# HardwareTutorial-Controller_Board_Interf.net
KiCad netlist of a schematic drawn in Altium Designer
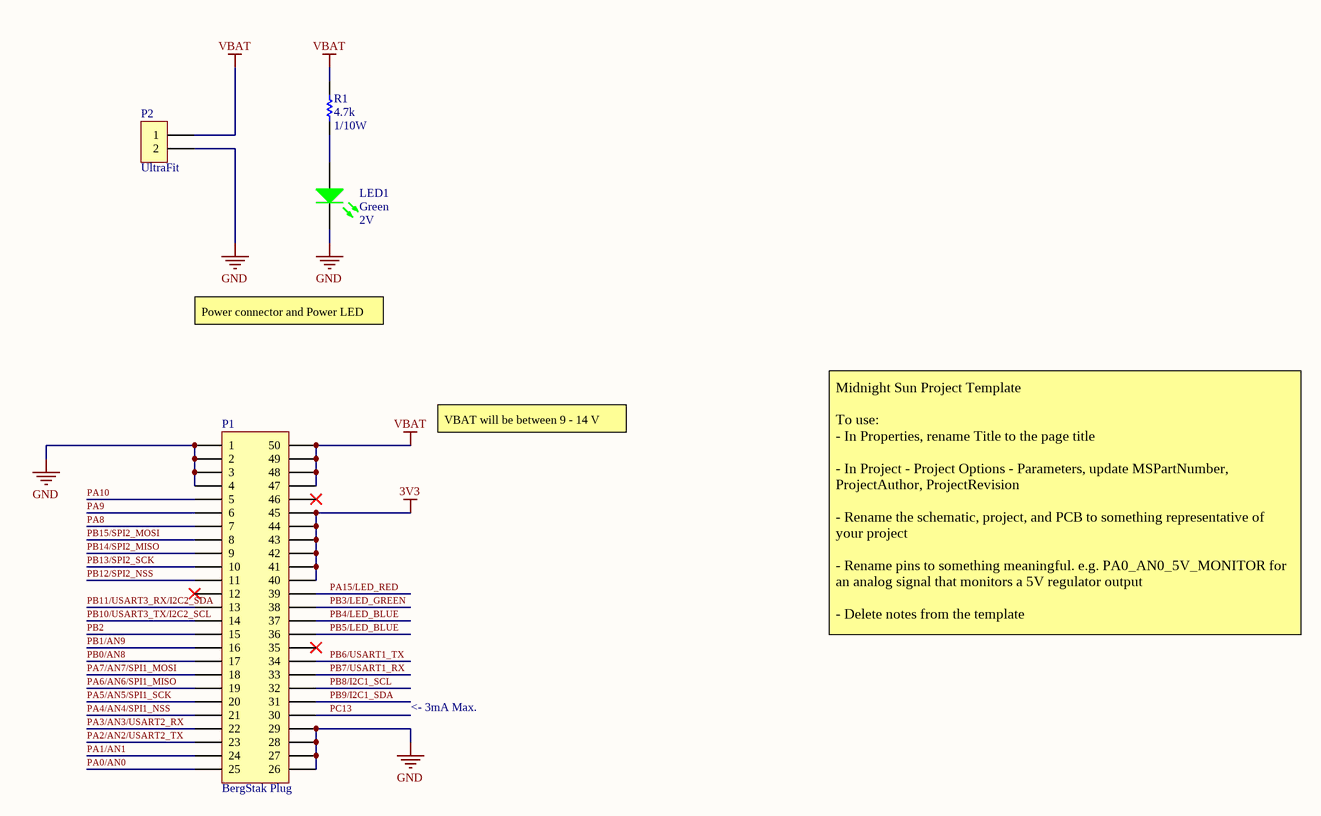
[diagram p0: HardwareTutorial-Controller_Board_Interface.SchDoc]

(export (version "E")
  (design (tool "Eeschema 10.0.6"))
  (components
    (comp (ref "LED1")
      (value "LED GREEN CLEAR 2V 0603")
      (footprint "LED_0603")
      (description "Green 572nm LED Indication - Discrete 2V 0603 (1608 Metric)")
      (fields
        (field (name "MANUFACTURER") "Wurth Electronics Inc.")
        (field (name "MANUFACTURER PART NUMBER") "150060VS75000")
        (field (name "COLOR") "Green")
        (field (name "VOLTAGE - FORWARD (VF) (TYP)") "2V")
      )
      (libsource (lib "Schematic Diagrams") (part "LED GREEN CLEAR 2V 0603"))
    )
    (comp (ref "P1")
      (value "CONN 50POS Bergstak Plug 0.02\"")
      (footprint "CONN, Bergstak 50 Pos Plug")
      (description "50 Position Connector Plug, Outer Shroud Contacts Surface Mount Gold")
      (fields (field (name "SERIES") "BergStak Plug"))
      (libsource (lib "Schematic Diagrams") (part "CONN 50POS Bergstak Plug 0.02{dblquote}"))
    )
    (comp (ref "P2")
      (value "CONN 2POS ULTRA-FIT 0.138\"")
      (footprint "CONN, 2POS ULTRA-FIT")
      (description "Connector Header Through Hole 2 position 0.138\" (3.50mm)")
      (fields
        (field (name "MANUFACTURER") "Molex")
        (field (name "MANUFACTURER PART NUMBER") "1722871102")
        (field (name "SERIES") "UltraFit")
      )
      (libsource (lib "Schematic Diagrams") (part "CONN 2POS ULTRA-FIT 0.138{dblquote}"))
    )
    (comp (ref "R1")
      (value "RES 4.7K OHM 1% 1/10W 0603")
      (footprint "RES, 0603")
      (description "4.7k Ohm ±1% 0.1W, 1/10W Chip Resistor 0603 (1608 Metric) Moisture Resistant Thick Film")
      (fields
        (field (name "TOLERANCE") "±1%")
        (field (name "RESISTANCE (OHMS)") "4.7k")
        (field (name "POWER (WATTS)") "1/10W")
      )
      (libsource (lib "Schematic Diagrams") (part "RES 4.7K OHM 1% 1/10W 0603"))
    )
  )
  (nets
    (net (code "1") (name "/PA0{slash}AN0") (class "Default")
      (node (ref "P1") (pin "25") (pinfunction "25_25") (pintype "passive"))
    )
    (net (code "2") (name "/PA1{slash}AN1") (class "Default")
      (node (ref "P1") (pin "24") (pinfunction "24_24") (pintype "passive"))
    )
    (net (code "3") (name "/PA2{slash}AN2{slash}USART2_TX") (class "Default")
      (node (ref "P1") (pin "23") (pinfunction "23_23") (pintype "passive"))
    )
    (net (code "4") (name "/PA3{slash}AN3{slash}USART2_RX") (class "Default")
      (node (ref "P1") (pin "22") (pinfunction "22_22") (pintype "passive"))
    )
    (net (code "5") (name "/PA4{slash}AN4{slash}SPI1_NSS") (class "Default")
      (node (ref "P1") (pin "21") (pinfunction "21_21") (pintype "passive"))
    )
    (net (code "6") (name "/PA5{slash}AN5{slash}SPI1_SCK") (class "Default")
      (node (ref "P1") (pin "20") (pinfunction "20_20") (pintype "passive"))
    )
    (net (code "7") (name "/PA6{slash}AN6{slash}SPI1_MISO") (class "Default")
      (node (ref "P1") (pin "19") (pinfunction "19_19") (pintype "passive"))
    )
    (net (code "8") (name "/PA7{slash}AN7{slash}SPI1_MOSI") (class "Default")
      (node (ref "P1") (pin "18") (pinfunction "18_18") (pintype "passive"))
    )
    (net (code "9") (name "/PA8") (class "Default")
      (node (ref "P1") (pin "7") (pinfunction "7_7") (pintype "passive"))
    )
    (net (code "10") (name "/PA9") (class "Default")
      (node (ref "P1") (pin "6") (pinfunction "6_6") (pintype "passive"))
    )
    (net (code "11") (name "/PA10") (class "Default")
      (node (ref "P1") (pin "5") (pinfunction "5_5") (pintype "passive"))
    )
    (net (code "12") (name "/PA15{slash}LED_RED") (class "Default")
      (node (ref "P1") (pin "39") (pinfunction "39_39") (pintype "passive"))
    )
    (net (code "13") (name "/PB0{slash}AN8") (class "Default")
      (node (ref "P1") (pin "17") (pinfunction "17_17") (pintype "passive"))
    )
    (net (code "14") (name "/PB1{slash}AN9") (class "Default")
      (node (ref "P1") (pin "16") (pinfunction "16_16") (pintype "passive"))
    )
    (net (code "15") (name "/PB2") (class "Default")
      (node (ref "P1") (pin "15") (pinfunction "15_15") (pintype "passive"))
    )
    (net (code "16") (name "/PB3{slash}LED_GREEN") (class "Default")
      (node (ref "P1") (pin "38") (pinfunction "38_38") (pintype "passive"))
    )
    (net (code "17") (name "/PB4{slash}LED_BLUE") (class "Default")
      (node (ref "P1") (pin "37") (pinfunction "37_37") (pintype "passive"))
    )
    (net (code "18") (name "/PB5{slash}LED_BLUE") (class "Default")
      (node (ref "P1") (pin "36") (pinfunction "36_36") (pintype "passive"))
    )
    (net (code "19") (name "/PB6{slash}USART1_TX") (class "Default")
      (node (ref "P1") (pin "34") (pinfunction "34_34") (pintype "passive"))
    )
    (net (code "20") (name "/PB7{slash}USART1_RX") (class "Default")
      (node (ref "P1") (pin "33") (pinfunction "33_33") (pintype "passive"))
    )
    (net (code "21") (name "/PB8{slash}I2C1_SCL") (class "Default")
      (node (ref "P1") (pin "32") (pinfunction "32_32") (pintype "passive"))
    )
    (net (code "22") (name "/PB9{slash}I2C1_SDA") (class "Default")
      (node (ref "P1") (pin "31") (pinfunction "31_31") (pintype "passive"))
    )
    (net (code "23") (name "/PB10{slash}USART3_TX{slash}I2C2_SCL") (class "Default")
      (node (ref "P1") (pin "14") (pinfunction "14_14") (pintype "passive"))
    )
    (net (code "24") (name "/PB11{slash}USART3_RX{slash}I2C2_SDA") (class "Default")
      (node (ref "P1") (pin "13") (pinfunction "13_13") (pintype "passive"))
    )
    (net (code "25") (name "/PB12{slash}SPI2_NSS") (class "Default")
      (node (ref "P1") (pin "11") (pinfunction "11_11") (pintype "passive"))
    )
    (net (code "26") (name "/PB13{slash}SPI2_SCK") (class "Default")
      (node (ref "P1") (pin "10") (pinfunction "10_10") (pintype "passive"))
    )
    (net (code "27") (name "/PB14{slash}SPI2_MISO") (class "Default")
      (node (ref "P1") (pin "9") (pinfunction "9_9") (pintype "passive"))
    )
    (net (code "28") (name "/PB15{slash}SPI2_MOSI") (class "Default")
      (node (ref "P1") (pin "8") (pinfunction "8_8") (pintype "passive"))
    )
    (net (code "29") (name "/PC13") (class "Default")
      (node (ref "P1") (pin "30") (pinfunction "30_30") (pintype "passive"))
    )
    (net (code "30") (name "3V3") (class "Default")
      (node (ref "P1") (pin "40") (pinfunction "40_40") (pintype "passive"))
      (node (ref "P1") (pin "41") (pinfunction "41_41") (pintype "passive"))
      (node (ref "P1") (pin "42") (pinfunction "42_42") (pintype "passive"))
      (node (ref "P1") (pin "43") (pinfunction "43_43") (pintype "passive"))
      (node (ref "P1") (pin "44") (pinfunction "44_44") (pintype "passive"))
      (node (ref "P1") (pin "45") (pinfunction "45_45") (pintype "passive"))
    )
    (net (code "31") (name "GND") (class "Default")
      (node (ref "LED1") (pin "2") (pinfunction "K_2") (pintype "passive"))
      (node (ref "P1") (pin "1") (pinfunction "1_1") (pintype "passive"))
      (node (ref "P1") (pin "2") (pinfunction "2_2") (pintype "passive"))
      (node (ref "P1") (pin "26") (pinfunction "26_26") (pintype "passive"))
      (node (ref "P1") (pin "27") (pinfunction "27_27") (pintype "passive"))
      (node (ref "P1") (pin "28") (pinfunction "28_28") (pintype "passive"))
      (node (ref "P1") (pin "29") (pinfunction "29_29") (pintype "passive"))
      (node (ref "P1") (pin "3") (pinfunction "3_3") (pintype "passive"))
      (node (ref "P1") (pin "4") (pinfunction "4_4") (pintype "passive"))
      (node (ref "P2") (pin "2") (pinfunction "2_2") (pintype "passive"))
    )
    (net (code "32") (name "Net-(LED1-A)") (class "Default")
      (node (ref "LED1") (pin "1") (pinfunction "A_1") (pintype "passive"))
      (node (ref "R1") (pin "2") (pinfunction "2_2") (pintype "passive"))
    )
    (net (code "33") (name "VBAT") (class "Default")
      (node (ref "P1") (pin "47") (pinfunction "47_47") (pintype "passive"))
      (node (ref "P1") (pin "48") (pinfunction "48_48") (pintype "passive"))
      (node (ref "P1") (pin "49") (pinfunction "49_49") (pintype "passive"))
      (node (ref "P1") (pin "50") (pinfunction "50_50") (pintype "passive"))
      (node (ref "P2") (pin "1") (pinfunction "1_1") (pintype "passive"))
      (node (ref "R1") (pin "1") (pinfunction "1_1") (pintype "passive"))
    )
    (net (code "34") (name "unconnected-(P1-Pad12)") (class "Default")
      (node (ref "P1") (pin "12") (pinfunction "12_12") (pintype "passive+no_connect"))
    )
    (net (code "35") (name "unconnected-(P1-Pad35)") (class "Default")
      (node (ref "P1") (pin "35") (pinfunction "35_35") (pintype "passive+no_connect"))
    )
    (net (code "36") (name "unconnected-(P1-Pad46)") (class "Default")
      (node (ref "P1") (pin "46") (pinfunction "46_46") (pintype "passive+no_connect"))
    )
  )
)
